# Driver.net
KiCad netlist of a schematic drawn in EAGLE
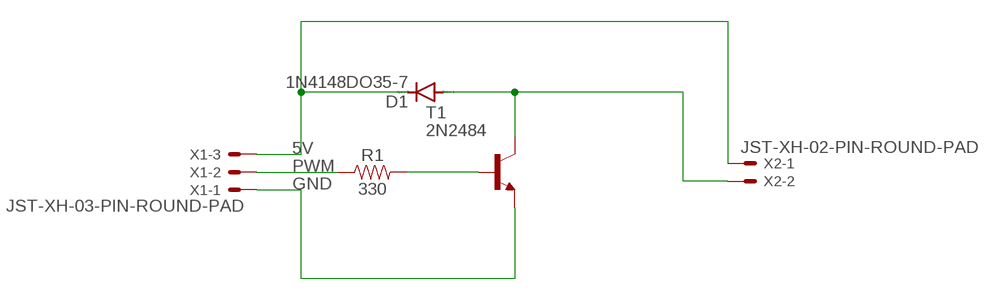
[diagram p0: schematic, sheet 1]

(export (version "E")
  (design (tool "Eeschema 10.0.6"))
  (components
    (comp (ref "D1")
      (value "1N4148DO35-7")
      (footprint "eagle-import:DO35-7")
      (libsource (lib "eagle-import") (part "1N4148DO35-7"))
    )
    (comp (ref "R1")
      (value "330")
      (footprint "eagle-import:AXIAL-0.3")
      (libsource (lib "eagle-import") (part "330OHM-HORIZ-1/10W-5%"))
    )
    (comp (ref "T1")
      (value "2N2484")
      (footprint "eagle-import:TO18")
      (libsource (lib "eagle-import") (part "2N2484"))
    )
    (comp (ref "X1")
      (value "JST-XH-03-PIN-ROUND-PAD")
      (footprint "eagle-import:JST-XH-03-PACKAGE-ROUND-PAD")
      (libsource (lib "eagle-import") (part "JST-XH-03-PIN-ROUND-PAD"))
    )
    (comp (ref "X2")
      (value "JST-XH-02-PIN-ROUND-PAD")
      (footprint "eagle-import:JST-XH-02-PACKAGE-ROUND-PAD")
      (libsource (lib "eagle-import") (part "JST-XH-02-PIN-ROUND-PAD"))
    )
  )
  (nets
    (net (code "1") (name "/5V") (class "Default")
      (node (ref "D1") (pin "C") (pinfunction "C_C") (pintype "passive"))
      (node (ref "X1") (pin "3") (pinfunction "S_3") (pintype "passive"))
      (node (ref "X2") (pin "1") (pinfunction "S_1") (pintype "passive"))
    )
    (net (code "2") (name "/GND") (class "Default")
      (node (ref "T1") (pin "1") (pinfunction "E_1") (pintype "passive"))
      (node (ref "X1") (pin "1") (pinfunction "S_1") (pintype "passive"))
    )
    (net (code "3") (name "/PWM") (class "Default")
      (node (ref "R1") (pin "P$1") (pinfunction "1_P$1") (pintype "passive"))
      (node (ref "X1") (pin "2") (pinfunction "S_2") (pintype "passive"))
    )
    (net (code "4") (name "Net-(R1-2)") (class "Default")
      (node (ref "R1") (pin "P$2") (pinfunction "2_P$2") (pintype "passive"))
      (node (ref "T1") (pin "2") (pinfunction "B_2") (pintype "passive"))
    )
    (net (code "5") (name "Net-(T1-C)") (class "Default")
      (node (ref "D1") (pin "A") (pinfunction "A_A") (pintype "passive"))
      (node (ref "T1") (pin "3") (pinfunction "C_3") (pintype "passive"))
      (node (ref "X2") (pin "2") (pinfunction "S_2") (pintype "passive"))
    )
  )
)
